# Sheet1.net
KiCad netlist of a schematic drawn in Altium Designer
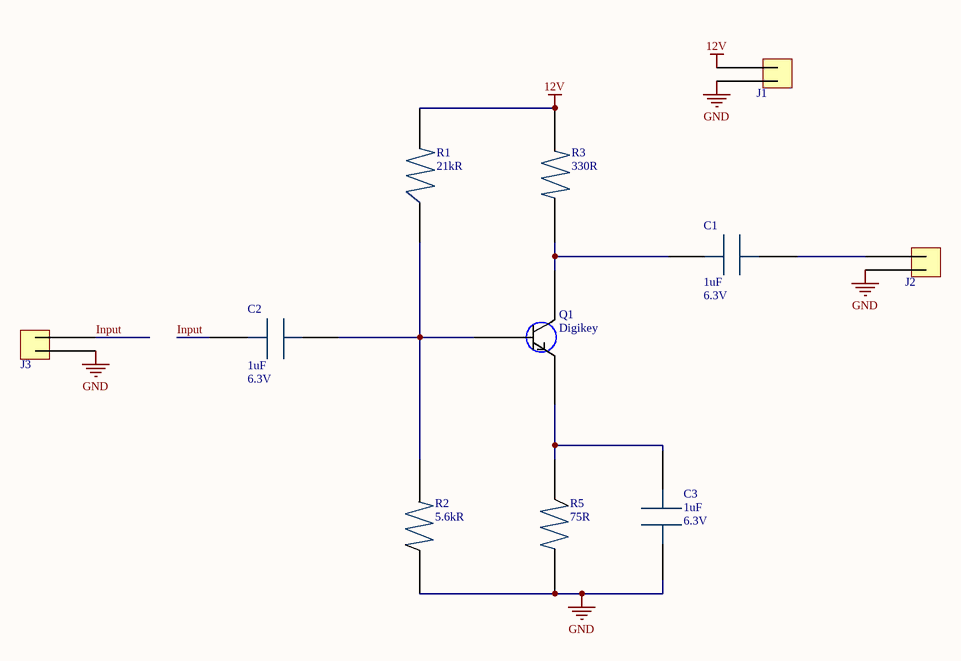
[diagram p0: Sheet1.SchDoc]

(export (version "E")
  (design (tool "Eeschema 10.0.6"))
  (components
    (comp (ref "C1")
      (value "1uF")
      (footprint "C0805C105K9RACTU")
      (fields
        (field (name "MANUFACTURER") "KEMET")
        (field (name "MANUFACTURER PART NUMBER") "C0805C105K9RACTU")
        (field (name "VOLTAGE") "6.3V")
      )
      (libsource (lib "Demo_intrgrated_lib") (part "C0805C105K9RACTU"))
    )
    (comp (ref "C2")
      (value "1uF")
      (footprint "C0805C105K9RACTU")
      (fields
        (field (name "MANUFACTURER") "KEMET")
        (field (name "MANUFACTURER PART NUMBER") "C0805C105K9RACTU")
        (field (name "VOLTAGE") "6.3V")
      )
      (libsource (lib "Demo_intrgrated_lib") (part "C0805C105K9RACTU"))
    )
    (comp (ref "C3")
      (value "1uF")
      (footprint "C0805C105K9RACTU")
      (fields
        (field (name "MANUFACTURER") "KEMET")
        (field (name "MANUFACTURER PART NUMBER") "C0805C105K9RACTU")
        (field (name "VOLTAGE") "6.3V")
      )
      (libsource (lib "Demo_intrgrated_lib") (part "C0805C105K9RACTU"))
    )
    (comp (ref "J1")
      (value "OSTTE020104")
      (footprint "OST_OSTTE020104")
      (description "Barrier Strip Terminal Block, 10A, 1 Row(s), 1 Deck(s)")
      (fields (field (name "MANUFACTURER") "On-Shore Technology") (field (name "SAFETY APPROVAL") "UL,CUL"))
      (libsource (lib "Demo_intrgrated_lib") (part "OSTTE020104"))
    )
    (comp (ref "J2")
      (value "OSTTE020104")
      (footprint "OST_OSTTE020104")
      (description "Barrier Strip Terminal Block, 10A, 1 Row(s), 1 Deck(s)")
      (fields (field (name "MANUFACTURER") "On-Shore Technology") (field (name "SAFETY APPROVAL") "UL,CUL"))
      (libsource (lib "Demo_intrgrated_lib") (part "OSTTE020104"))
    )
    (comp (ref "J3")
      (value "OSTTE020104")
      (footprint "OST_OSTTE020104")
      (description "Barrier Strip Terminal Block, 10A, 1 Row(s), 1 Deck(s)")
      (fields (field (name "MANUFACTURER") "On-Shore Technology") (field (name "SAFETY APPROVAL") "UL,CUL"))
      (libsource (lib "") (part "OSTTE020104_1"))
    )
    (comp (ref "Q1")
      (value "BC547BBU")
      (footprint "TO92127P476H533-3 - duplicate")
      (description "Small Signal Bipolar Transistor, 0.1A I(C), 45V V(BR)CEO, 1-Element, NPN, Silicon, TO-92")
      (fields
        (field (name "MANUFACTURER") "ON Semiconductor / Fairchild")
        (field (name "SUPPLIER") "Digikey")
      )
      (libsource (lib "Demo_intrgrated_lib") (part "BC547BBU"))
    )
    (comp (ref "R1")
      (value "21kR")
      (footprint "RC0805FR-0721KL")
      (fields
        (field (name "MANUFACTURER") "Yageo")
        (field (name "MANUFACTURER PART NUMBER") "RC0805FR-0721KL")
        (field (name "TOLERANCE") "1%")
      )
      (libsource (lib "Demo_intrgrated_lib") (part "RC0805FR-0721KL"))
    )
    (comp (ref "R2")
      (value "5.6kR")
      (footprint "RC0805FR-075K6L")
      (fields
        (field (name "MANUFACTURER") "Yageo")
        (field (name "MANUFACTURER PART NUMBER") "RC0805FR-075K6L")
        (field (name "TOLERANCE") "1%")
      )
      (libsource (lib "Demo_intrgrated_lib") (part "RC0805FR-075K6L"))
    )
    (comp (ref "R3")
      (value "330R")
      (footprint "RC0805FR-07330RL")
      (fields
        (field (name "MANUFACTURER") "Yageo")
        (field (name "MANUFACTURER PART NUMBER") "RC0805FR-07330RL")
        (field (name "TOLERANCE") "1%")
      )
      (libsource (lib "Demo_intrgrated_lib") (part "RC0805FR-07330RL"))
    )
    (comp (ref "R5")
      (value "75R")
      (footprint "RC0805FR-0775RL")
      (fields
        (field (name "MANUFACTURER") "Yageo")
        (field (name "MANUFACTURER PART NUMBER") "RC0805FR-0775RL")
        (field (name "TOLERANCE") "1%")
      )
      (libsource (lib "Demo_intrgrated_lib") (part "RC0805FR-0775RL"))
    )
  )
  (nets
    (net (code "1") (name "/Input") (class "Default")
      (node (ref "C2") (pin "2") (pinfunction "2_2") (pintype "passive"))
      (node (ref "J3") (pin "2") (pinfunction "2_2") (pintype "passive"))
    )
    (net (code "2") (name "12V") (class "Default")
      (node (ref "J1") (pin "1") (pinfunction "1_1") (pintype "passive"))
      (node (ref "R1") (pin "2") (pinfunction "2_2") (pintype "passive"))
      (node (ref "R3") (pin "2") (pinfunction "2_2") (pintype "passive"))
    )
    (net (code "3") (name "GND") (class "Default")
      (node (ref "C3") (pin "1") (pinfunction "1_1") (pintype "passive"))
      (node (ref "J1") (pin "2") (pinfunction "2_2") (pintype "passive"))
      (node (ref "J2") (pin "2") (pinfunction "2_2") (pintype "passive"))
      (node (ref "J3") (pin "1") (pinfunction "1_1") (pintype "passive"))
      (node (ref "R2") (pin "1") (pinfunction "1_1") (pintype "passive"))
      (node (ref "R5") (pin "2") (pinfunction "2_2") (pintype "passive"))
    )
    (net (code "4") (name "Net-(C1-Pad1)") (class "Default")
      (node (ref "C1") (pin "1") (pinfunction "1_1") (pintype "passive"))
      (node (ref "Q1") (pin "2") (pinfunction "2_2") (pintype "passive"))
      (node (ref "R3") (pin "1") (pinfunction "1_1") (pintype "passive"))
    )
    (net (code "5") (name "Net-(C1-Pad2)") (class "Default")
      (node (ref "C1") (pin "2") (pinfunction "2_2") (pintype "passive"))
      (node (ref "J2") (pin "1") (pinfunction "1_1") (pintype "passive"))
    )
    (net (code "6") (name "Net-(C2-Pad1)") (class "Default")
      (node (ref "C2") (pin "1") (pinfunction "1_1") (pintype "passive"))
      (node (ref "Q1") (pin "1") (pinfunction "1_1") (pintype "passive"))
      (node (ref "R1") (pin "1") (pinfunction "1_1") (pintype "passive"))
      (node (ref "R2") (pin "2") (pinfunction "2_2") (pintype "passive"))
    )
    (net (code "7") (name "Net-(C3-Pad2)") (class "Default")
      (node (ref "C3") (pin "2") (pinfunction "2_2") (pintype "passive"))
      (node (ref "Q1") (pin "3") (pinfunction "3_3") (pintype "passive"))
      (node (ref "R5") (pin "1") (pinfunction "1_1") (pintype "passive"))
    )
  )
)
